# oresat-batteries-inhibits-blockdiagram.net
KiCad netlist of a schematic drawn in EAGLE
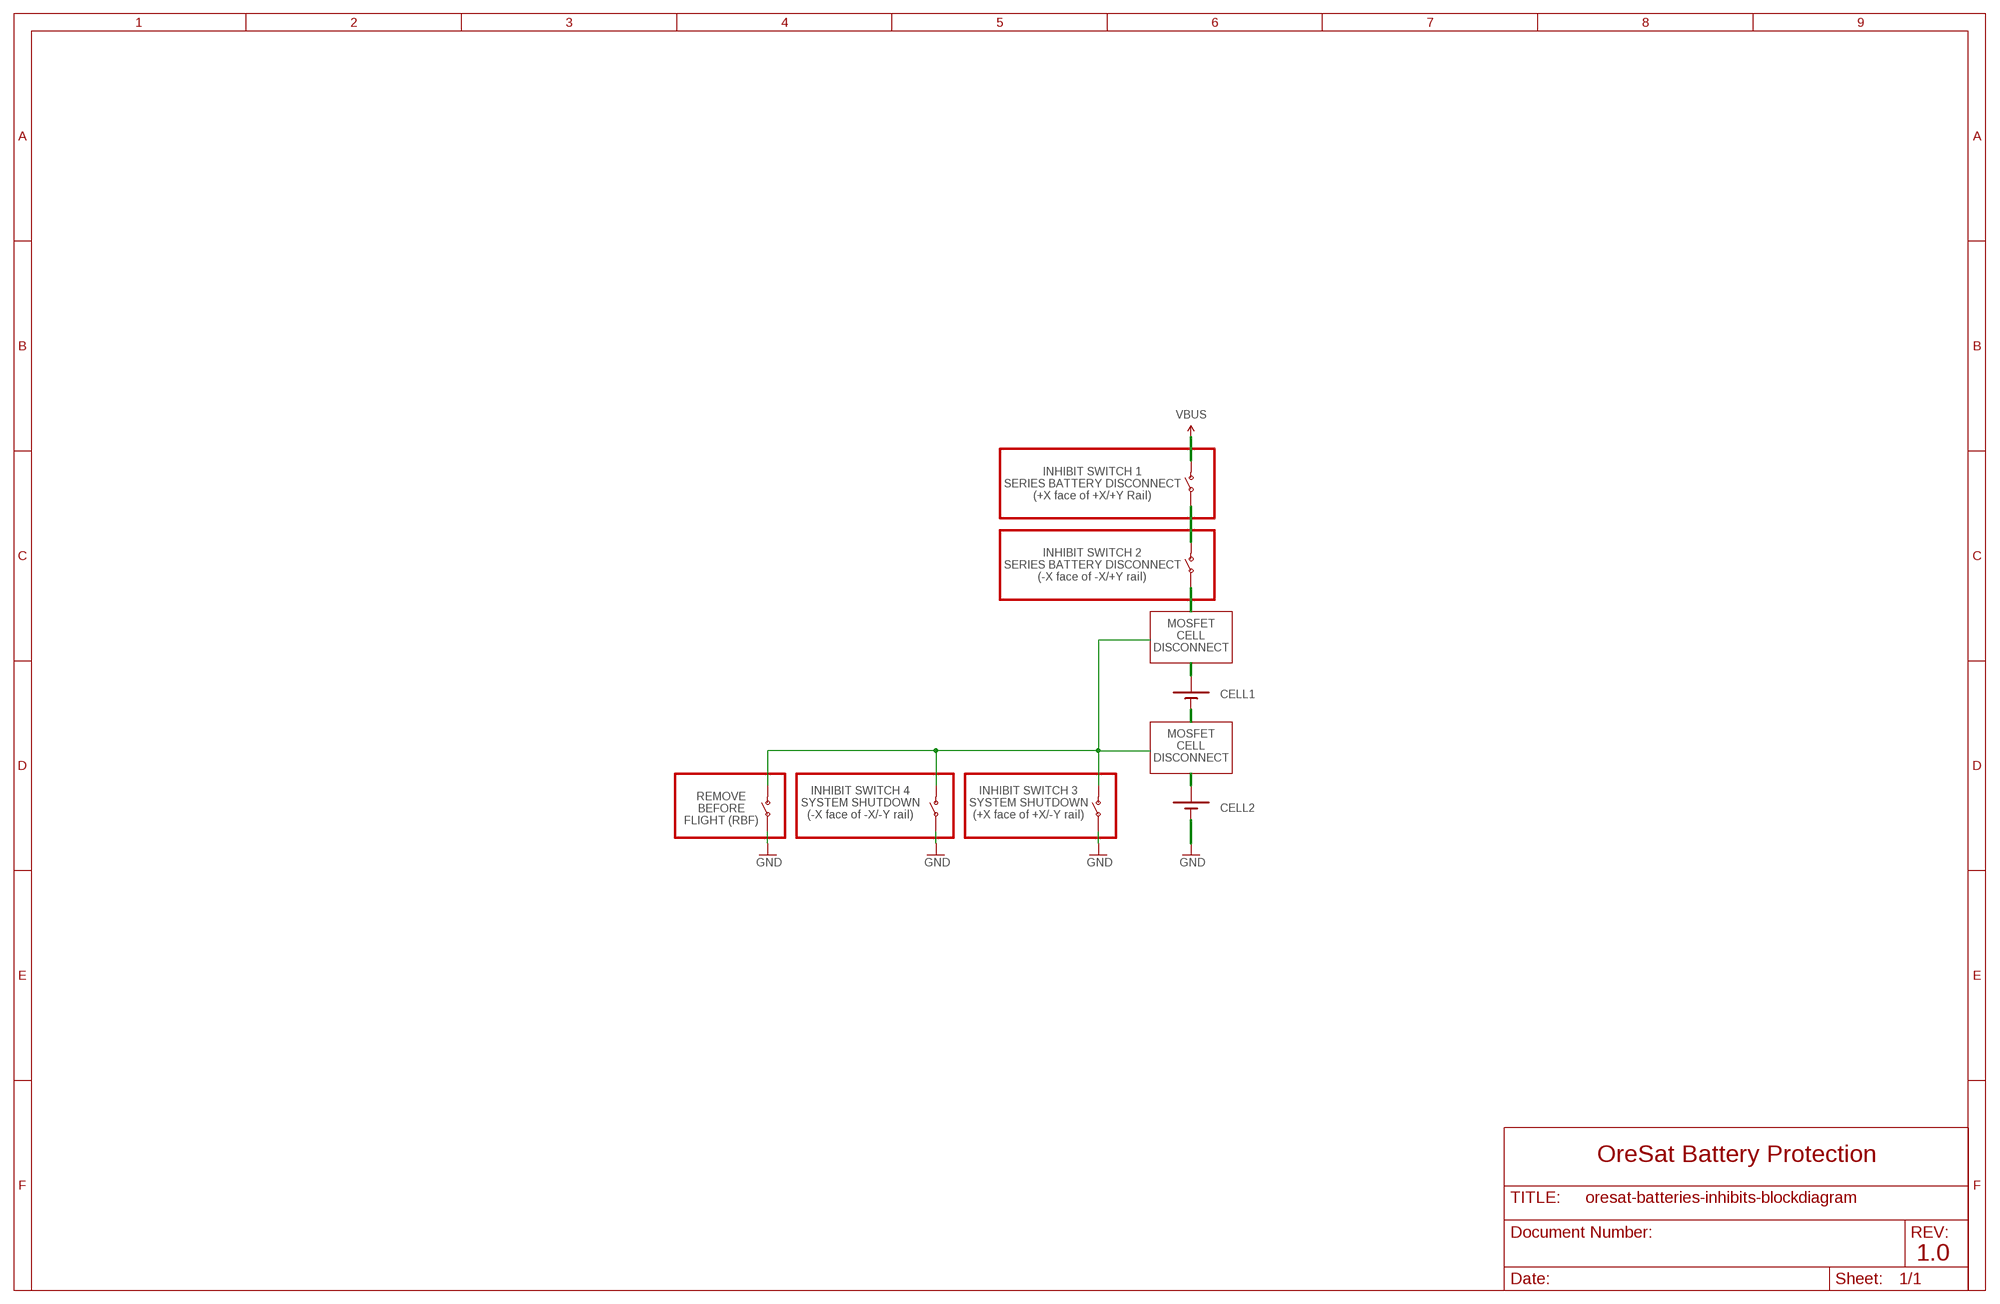
[diagram p0: schematic, sheet 1]

(export (version "E")
  (design (tool "Eeschema 10.0.6"))
  (components
    (comp (ref "CELL1")
      (value "B-18650-LI-BATTERY")
      (footprint "eagle-import:18650")
      (fields (field (name "MFR") "Tenergy") (field (name "MPN") "MH48285"))
      (libsource (lib "eagle-import") (part "B-18650-LI-BATTERY"))
    )
    (comp (ref "CELL2")
      (value "B-18650-LI-BATTERY")
      (footprint "eagle-import:18650")
      (fields (field (name "MFR") "Tenergy") (field (name "MPN") "MH48285"))
      (libsource (lib "eagle-import") (part "B-18650-LI-BATTERY"))
    )
    (comp (ref "U$1")
      (value "SWITCH-SPST-2TV")
      (footprint "eagle-import:SWITCH-SPST-VERTICAL")
      (libsource (lib "eagle-import") (part "SWITCH-SPST-2TV"))
    )
    (comp (ref "U$2")
      (value "SWITCH-SPST-2TV")
      (footprint "eagle-import:SWITCH-SPST-VERTICAL")
      (libsource (lib "eagle-import") (part "SWITCH-SPST-2TV"))
    )
    (comp (ref "U$3")
      (value "SWITCH-SPST-2TV")
      (footprint "eagle-import:SWITCH-SPST-VERTICAL")
      (libsource (lib "eagle-import") (part "SWITCH-SPST-2TV"))
    )
    (comp (ref "U$4")
      (value "SWITCH-SPST-2TV")
      (footprint "eagle-import:SWITCH-SPST-VERTICAL")
      (libsource (lib "eagle-import") (part "SWITCH-SPST-2TV"))
    )
    (comp (ref "U$5")
      (value "SWITCH-SPST-2TV")
      (footprint "eagle-import:SWITCH-SPST-VERTICAL")
      (libsource (lib "eagle-import") (part "SWITCH-SPST-2TV"))
    )
  )
  (nets
    (net (code "1") (name "GND") (class "Default")
      (node (ref "CELL2") (pin "NEG-T") (pinfunction "NEG_NEG-T") (pintype "power_in"))
      (node (ref "U$2") (pin "2") (pinfunction "P_2") (pintype "passive"))
      (node (ref "U$3") (pin "2") (pinfunction "P_2") (pintype "passive"))
      (node (ref "U$5") (pin "2") (pinfunction "P_2") (pintype "passive"))
    )
    (net (code "2") (name "Net-(U$1-O)") (class "Default")
      (node (ref "U$1") (pin "1") (pinfunction "O_1") (pintype "passive"))
      (node (ref "U$4") (pin "2") (pinfunction "P_2") (pintype "passive"))
    )
    (net (code "3") (name "Net-(U$2-O)") (class "Default")
      (node (ref "U$2") (pin "1") (pinfunction "O_1") (pintype "passive"))
      (node (ref "U$3") (pin "1") (pinfunction "O_1") (pintype "passive"))
      (node (ref "U$5") (pin "1") (pinfunction "O_1") (pintype "passive"))
    )
    (net (code "4") (name "VBUS") (class "Default")
      (node (ref "U$4") (pin "1") (pinfunction "O_1") (pintype "passive"))
    )
    (net (code "5") (name "unconnected-(CELL1-NEG-PadNEG-T)") (class "Default")
      (node (ref "CELL1") (pin "NEG-T") (pinfunction "NEG_NEG-T") (pintype "power_in"))
    )
    (net (code "6") (name "unconnected-(CELL1-POS-PadPOS-T)") (class "Default")
      (node (ref "CELL1") (pin "POS-T") (pinfunction "POS_POS-T") (pintype "power_in"))
    )
    (net (code "7") (name "unconnected-(CELL2-POS-PadPOS-T)") (class "Default")
      (node (ref "CELL2") (pin "POS-T") (pinfunction "POS_POS-T") (pintype "power_in"))
    )
    (net (code "8") (name "unconnected-(U$1-P-Pad2)") (class "Default")
      (node (ref "U$1") (pin "2") (pinfunction "P_2") (pintype "passive"))
    )
  )
)
